# DaslightMux.net
KiCad netlist of a schematic drawn in EAGLE
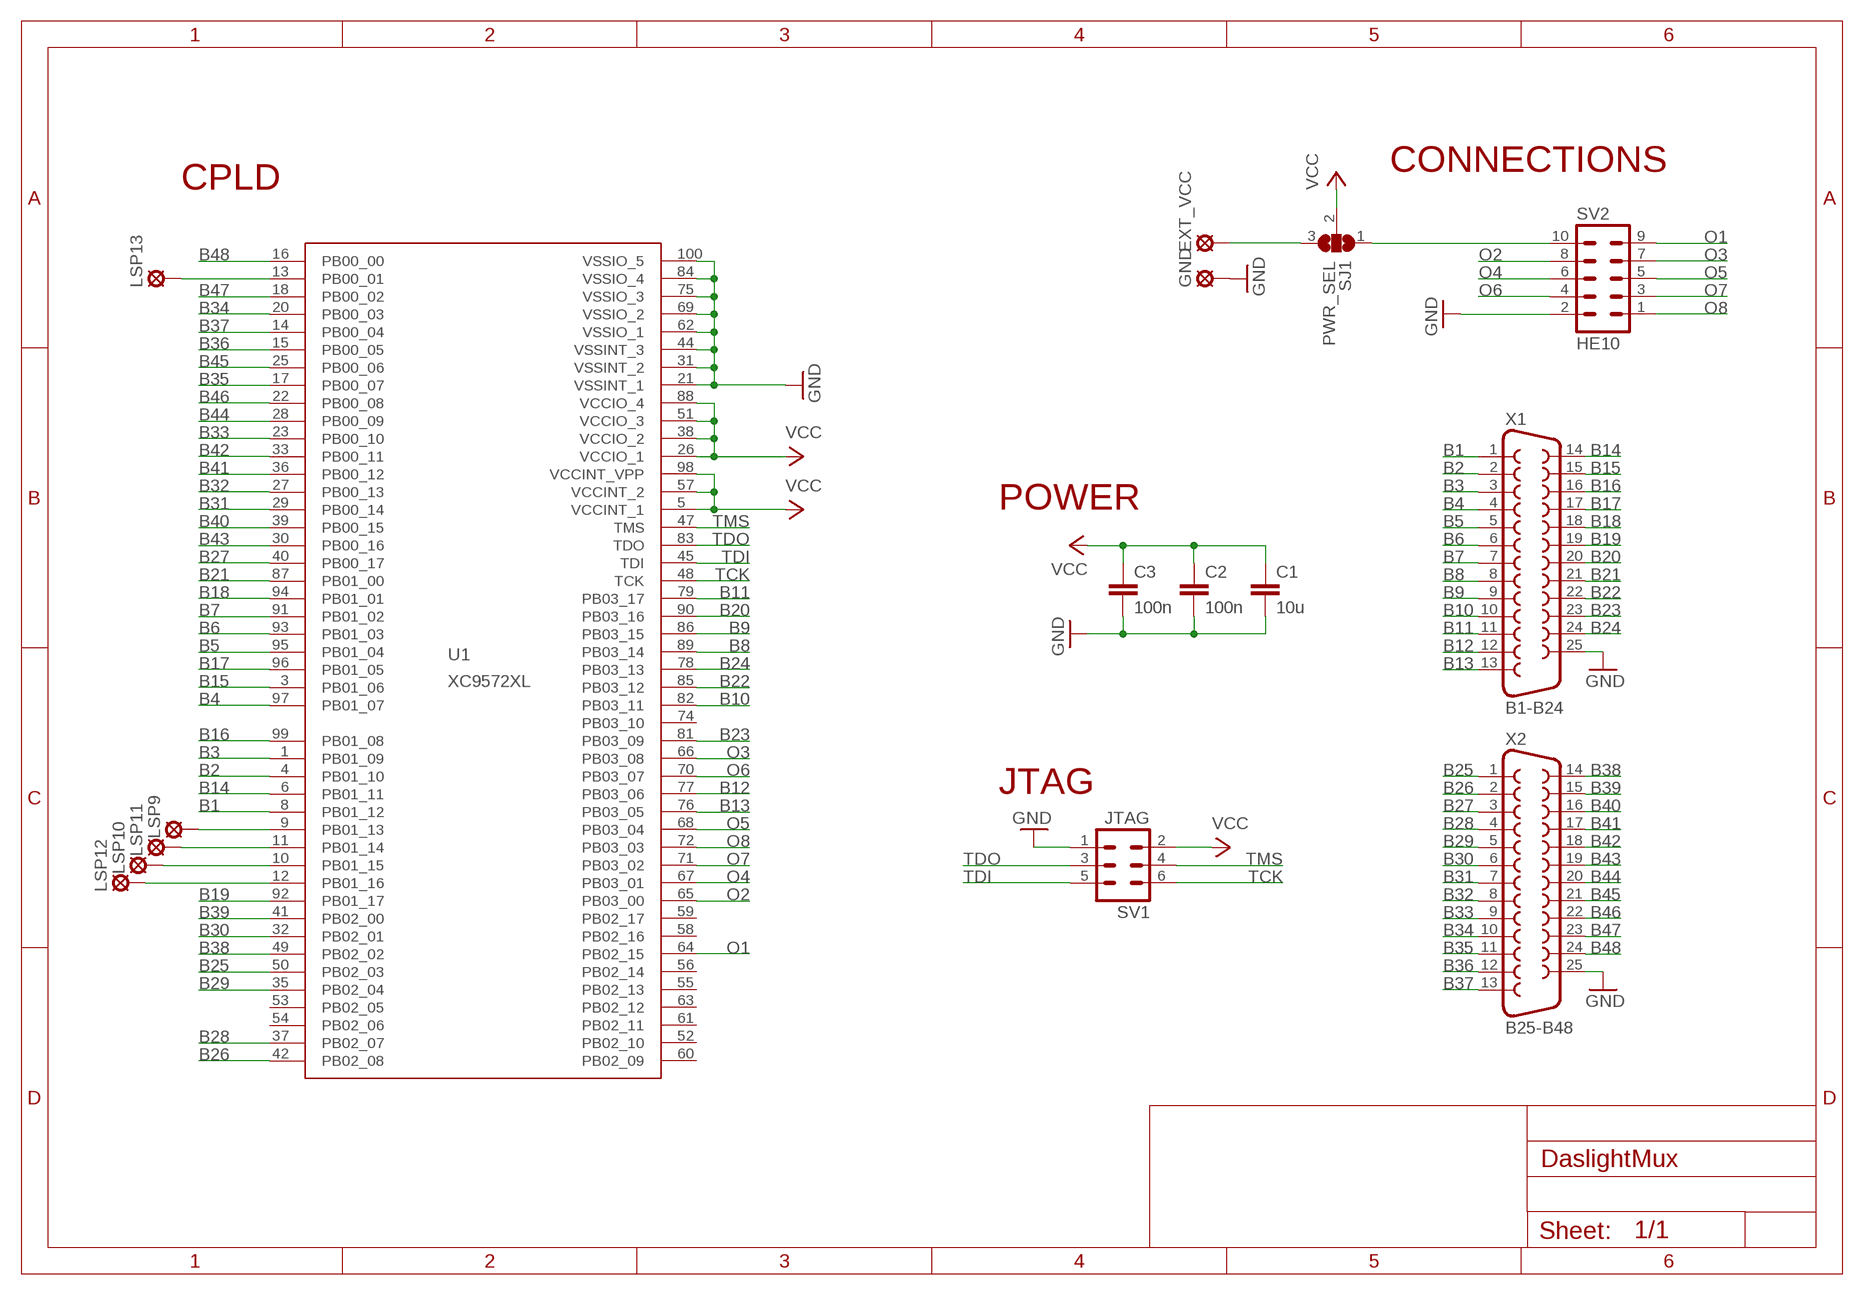
[diagram p0: schematic, sheet 1]

(export (version "E")
  (design (tool "Eeschema 10.0.6"))
  (components
    (comp (ref "C1")
      (value "10u")
      (footprint "eagle-import:C1206")
      (libsource (lib "eagle-import") (part "C-EUC1206"))
    )
    (comp (ref "C2")
      (value "100n")
      (footprint "eagle-import:C0603")
      (libsource (lib "eagle-import") (part "C-EUC0603"))
    )
    (comp (ref "C3")
      (value "100n")
      (footprint "eagle-import:C0603")
      (libsource (lib "eagle-import") (part "C-EUC0603"))
    )
    (comp (ref "EXT_VCC")
      (value "LSP10")
      (footprint "eagle-import:LSP10")
      (libsource (lib "eagle-import") (part "LSP10"))
    )
    (comp (ref "GND")
      (value "LSP10")
      (footprint "eagle-import:LSP10")
      (libsource (lib "eagle-import") (part "LSP10"))
    )
    (comp (ref "LSP9")
      (value "LSP10")
      (footprint "eagle-import:LSP10")
      (libsource (lib "eagle-import") (part "LSP10"))
    )
    (comp (ref "LSP10")
      (value "LSP10")
      (footprint "eagle-import:LSP10")
      (libsource (lib "eagle-import") (part "LSP10"))
    )
    (comp (ref "LSP11")
      (value "LSP10")
      (footprint "eagle-import:LSP10")
      (libsource (lib "eagle-import") (part "LSP10"))
    )
    (comp (ref "LSP12")
      (value "LSP10")
      (footprint "eagle-import:LSP10")
      (libsource (lib "eagle-import") (part "LSP10"))
    )
    (comp (ref "LSP13")
      (value "LSP10")
      (footprint "eagle-import:LSP10")
      (libsource (lib "eagle-import") (part "LSP10"))
    )
    (comp (ref "SJ1")
      (value "PWR_SEL")
      (footprint "eagle-import:SJ_2")
      (libsource (lib "eagle-import") (part "SJ2W"))
    )
    (comp (ref "SV1")
      (value "JTAG")
      (footprint "eagle-import:MA03-2")
      (libsource (lib "eagle-import") (part "MA03-2"))
    )
    (comp (ref "SV2")
      (value "HE10")
      (footprint "eagle-import:ML10L")
      (libsource (lib "eagle-import") (part "ML10L"))
    )
    (comp (ref "U1")
      (value "XC9572XL")
      (footprint "eagle-import:TQ100")
      (libsource (lib "eagle-import") (part "XC9572XL_TQ100"))
    )
    (comp (ref "X1")
      (value "B1-B24")
      (footprint "eagle-import:F25HP")
      (libsource (lib "eagle-import") (part "F25HP"))
    )
    (comp (ref "X2")
      (value "B25-B48")
      (footprint "eagle-import:F25HP")
      (libsource (lib "eagle-import") (part "F25HP"))
    )
  )
  (nets
    (net (code "1") (name "/B1") (class "Default")
      (node (ref "U1") (pin "8") (pinfunction "PB01_12_8") (pintype "bidirectional"))
      (node (ref "X1") (pin "1") (pinfunction "1_1") (pintype "passive"))
    )
    (net (code "2") (name "/B2") (class "Default")
      (node (ref "U1") (pin "4") (pinfunction "PB01_10_4") (pintype "bidirectional"))
      (node (ref "X1") (pin "2") (pinfunction "2_2") (pintype "passive"))
    )
    (net (code "3") (name "/B3") (class "Default")
      (node (ref "U1") (pin "1") (pinfunction "PB01_09_1") (pintype "bidirectional"))
      (node (ref "X1") (pin "3") (pinfunction "3_3") (pintype "passive"))
    )
    (net (code "4") (name "/B4") (class "Default")
      (node (ref "U1") (pin "97") (pinfunction "PB01_07_97") (pintype "bidirectional"))
      (node (ref "X1") (pin "4") (pinfunction "4_4") (pintype "passive"))
    )
    (net (code "5") (name "/B5") (class "Default")
      (node (ref "U1") (pin "95") (pinfunction "PB01_04_95") (pintype "bidirectional"))
      (node (ref "X1") (pin "5") (pinfunction "5_5") (pintype "passive"))
    )
    (net (code "6") (name "/B6") (class "Default")
      (node (ref "U1") (pin "93") (pinfunction "PB01_03_93") (pintype "bidirectional"))
      (node (ref "X1") (pin "6") (pinfunction "6_6") (pintype "passive"))
    )
    (net (code "7") (name "/B7") (class "Default")
      (node (ref "U1") (pin "91") (pinfunction "PB01_02_91") (pintype "bidirectional"))
      (node (ref "X1") (pin "7") (pinfunction "7_7") (pintype "passive"))
    )
    (net (code "8") (name "/B8") (class "Default")
      (node (ref "U1") (pin "89") (pinfunction "PB03_14_89") (pintype "bidirectional"))
      (node (ref "X1") (pin "8") (pinfunction "8_8") (pintype "passive"))
    )
    (net (code "9") (name "/B9") (class "Default")
      (node (ref "U1") (pin "86") (pinfunction "PB03_15_86") (pintype "bidirectional"))
      (node (ref "X1") (pin "9") (pinfunction "9_9") (pintype "passive"))
    )
    (net (code "10") (name "/B10") (class "Default")
      (node (ref "U1") (pin "82") (pinfunction "PB03_11_82") (pintype "bidirectional"))
      (node (ref "X1") (pin "10") (pinfunction "10_10") (pintype "passive"))
    )
    (net (code "11") (name "/B11") (class "Default")
      (node (ref "U1") (pin "79") (pinfunction "PB03_17_79") (pintype "bidirectional"))
      (node (ref "X1") (pin "11") (pinfunction "11_11") (pintype "passive"))
    )
    (net (code "12") (name "/B12") (class "Default")
      (node (ref "U1") (pin "77") (pinfunction "PB03_06_77") (pintype "bidirectional"))
      (node (ref "X1") (pin "12") (pinfunction "12_12") (pintype "passive"))
    )
    (net (code "13") (name "/B13") (class "Default")
      (node (ref "U1") (pin "76") (pinfunction "PB03_05_76") (pintype "bidirectional"))
      (node (ref "X1") (pin "13") (pinfunction "13_13") (pintype "passive"))
    )
    (net (code "14") (name "/B14") (class "Default")
      (node (ref "U1") (pin "6") (pinfunction "PB01_11_6") (pintype "bidirectional"))
      (node (ref "X1") (pin "14") (pinfunction "14_14") (pintype "passive"))
    )
    (net (code "15") (name "/B15") (class "Default")
      (node (ref "U1") (pin "3") (pinfunction "PB01_06_3") (pintype "bidirectional"))
      (node (ref "X1") (pin "15") (pinfunction "15_15") (pintype "passive"))
    )
    (net (code "16") (name "/B16") (class "Default")
      (node (ref "U1") (pin "99") (pinfunction "PB01_08_99") (pintype "bidirectional"))
      (node (ref "X1") (pin "16") (pinfunction "16_16") (pintype "passive"))
    )
    (net (code "17") (name "/B17") (class "Default")
      (node (ref "U1") (pin "96") (pinfunction "PB01_05_96") (pintype "bidirectional"))
      (node (ref "X1") (pin "17") (pinfunction "17_17") (pintype "passive"))
    )
    (net (code "18") (name "/B18") (class "Default")
      (node (ref "U1") (pin "94") (pinfunction "PB01_01_94") (pintype "bidirectional"))
      (node (ref "X1") (pin "18") (pinfunction "18_18") (pintype "passive"))
    )
    (net (code "19") (name "/B19") (class "Default")
      (node (ref "U1") (pin "92") (pinfunction "PB01_17_92") (pintype "bidirectional"))
      (node (ref "X1") (pin "19") (pinfunction "19_19") (pintype "passive"))
    )
    (net (code "20") (name "/B20") (class "Default")
      (node (ref "U1") (pin "90") (pinfunction "PB03_16_90") (pintype "bidirectional"))
      (node (ref "X1") (pin "20") (pinfunction "20_20") (pintype "passive"))
    )
    (net (code "21") (name "/B21") (class "Default")
      (node (ref "U1") (pin "87") (pinfunction "PB01_00_87") (pintype "bidirectional"))
      (node (ref "X1") (pin "21") (pinfunction "21_21") (pintype "passive"))
    )
    (net (code "22") (name "/B22") (class "Default")
      (node (ref "U1") (pin "85") (pinfunction "PB03_12_85") (pintype "bidirectional"))
      (node (ref "X1") (pin "22") (pinfunction "22_22") (pintype "passive"))
    )
    (net (code "23") (name "/B23") (class "Default")
      (node (ref "U1") (pin "81") (pinfunction "PB03_09_81") (pintype "bidirectional"))
      (node (ref "X1") (pin "23") (pinfunction "23_23") (pintype "passive"))
    )
    (net (code "24") (name "/B24") (class "Default")
      (node (ref "U1") (pin "78") (pinfunction "PB03_13_78") (pintype "bidirectional"))
      (node (ref "X1") (pin "24") (pinfunction "24_24") (pintype "passive"))
    )
    (net (code "25") (name "/B25") (class "Default")
      (node (ref "U1") (pin "50") (pinfunction "PB02_03_50") (pintype "bidirectional"))
      (node (ref "X2") (pin "1") (pinfunction "1_1") (pintype "passive"))
    )
    (net (code "26") (name "/B26") (class "Default")
      (node (ref "U1") (pin "42") (pinfunction "PB02_08_42") (pintype "bidirectional"))
      (node (ref "X2") (pin "2") (pinfunction "2_2") (pintype "passive"))
    )
    (net (code "27") (name "/B27") (class "Default")
      (node (ref "U1") (pin "40") (pinfunction "PB00_17_40") (pintype "bidirectional"))
      (node (ref "X2") (pin "3") (pinfunction "3_3") (pintype "passive"))
    )
    (net (code "28") (name "/B28") (class "Default")
      (node (ref "U1") (pin "37") (pinfunction "PB02_07_37") (pintype "bidirectional"))
      (node (ref "X2") (pin "4") (pinfunction "4_4") (pintype "passive"))
    )
    (net (code "29") (name "/B29") (class "Default")
      (node (ref "U1") (pin "35") (pinfunction "PB02_04_35") (pintype "bidirectional"))
      (node (ref "X2") (pin "5") (pinfunction "5_5") (pintype "passive"))
    )
    (net (code "30") (name "/B30") (class "Default")
      (node (ref "U1") (pin "32") (pinfunction "PB02_01_32") (pintype "bidirectional"))
      (node (ref "X2") (pin "6") (pinfunction "6_6") (pintype "passive"))
    )
    (net (code "31") (name "/B31") (class "Default")
      (node (ref "U1") (pin "29") (pinfunction "PB00_14_29") (pintype "bidirectional"))
      (node (ref "X2") (pin "7") (pinfunction "7_7") (pintype "passive"))
    )
    (net (code "32") (name "/B32") (class "Default")
      (node (ref "U1") (pin "27") (pinfunction "PB00_13_27") (pintype "bidirectional"))
      (node (ref "X2") (pin "8") (pinfunction "8_8") (pintype "passive"))
    )
    (net (code "33") (name "/B33") (class "Default")
      (node (ref "U1") (pin "23") (pinfunction "PB00_10_23") (pintype "bidirectional"))
      (node (ref "X2") (pin "9") (pinfunction "9_9") (pintype "passive"))
    )
    (net (code "34") (name "/B34") (class "Default")
      (node (ref "U1") (pin "20") (pinfunction "PB00_03_20") (pintype "bidirectional"))
      (node (ref "X2") (pin "10") (pinfunction "10_10") (pintype "passive"))
    )
    (net (code "35") (name "/B35") (class "Default")
      (node (ref "U1") (pin "17") (pinfunction "PB00_07_17") (pintype "bidirectional"))
      (node (ref "X2") (pin "11") (pinfunction "11_11") (pintype "passive"))
    )
    (net (code "36") (name "/B36") (class "Default")
      (node (ref "U1") (pin "15") (pinfunction "PB00_05_15") (pintype "bidirectional"))
      (node (ref "X2") (pin "12") (pinfunction "12_12") (pintype "passive"))
    )
    (net (code "37") (name "/B37") (class "Default")
      (node (ref "U1") (pin "14") (pinfunction "PB00_04_14") (pintype "bidirectional"))
      (node (ref "X2") (pin "13") (pinfunction "13_13") (pintype "passive"))
    )
    (net (code "38") (name "/B38") (class "Default")
      (node (ref "U1") (pin "49") (pinfunction "PB02_02_49") (pintype "bidirectional"))
      (node (ref "X2") (pin "14") (pinfunction "14_14") (pintype "passive"))
    )
    (net (code "39") (name "/B39") (class "Default")
      (node (ref "U1") (pin "41") (pinfunction "PB02_00_41") (pintype "bidirectional"))
      (node (ref "X2") (pin "15") (pinfunction "15_15") (pintype "passive"))
    )
    (net (code "40") (name "/B40") (class "Default")
      (node (ref "U1") (pin "39") (pinfunction "PB00_15_39") (pintype "bidirectional"))
      (node (ref "X2") (pin "16") (pinfunction "16_16") (pintype "passive"))
    )
    (net (code "41") (name "/B41") (class "Default")
      (node (ref "U1") (pin "36") (pinfunction "PB00_12_36") (pintype "bidirectional"))
      (node (ref "X2") (pin "17") (pinfunction "17_17") (pintype "passive"))
    )
    (net (code "42") (name "/B42") (class "Default")
      (node (ref "U1") (pin "33") (pinfunction "PB00_11_33") (pintype "bidirectional"))
      (node (ref "X2") (pin "18") (pinfunction "18_18") (pintype "passive"))
    )
    (net (code "43") (name "/B43") (class "Default")
      (node (ref "U1") (pin "30") (pinfunction "PB00_16_30") (pintype "bidirectional"))
      (node (ref "X2") (pin "19") (pinfunction "19_19") (pintype "passive"))
    )
    (net (code "44") (name "/B44") (class "Default")
      (node (ref "U1") (pin "28") (pinfunction "PB00_09_28") (pintype "bidirectional"))
      (node (ref "X2") (pin "20") (pinfunction "20_20") (pintype "passive"))
    )
    (net (code "45") (name "/B45") (class "Default")
      (node (ref "U1") (pin "25") (pinfunction "PB00_06_25") (pintype "bidirectional"))
      (node (ref "X2") (pin "21") (pinfunction "21_21") (pintype "passive"))
    )
    (net (code "46") (name "/B46") (class "Default")
      (node (ref "U1") (pin "22") (pinfunction "PB00_08_22") (pintype "bidirectional"))
      (node (ref "X2") (pin "22") (pinfunction "22_22") (pintype "passive"))
    )
    (net (code "47") (name "/B47") (class "Default")
      (node (ref "U1") (pin "18") (pinfunction "PB00_02_18") (pintype "bidirectional"))
      (node (ref "X2") (pin "23") (pinfunction "23_23") (pintype "passive"))
    )
    (net (code "48") (name "/B48") (class "Default")
      (node (ref "U1") (pin "16") (pinfunction "PB00_00_16") (pintype "bidirectional"))
      (node (ref "X2") (pin "24") (pinfunction "24_24") (pintype "passive"))
    )
    (net (code "49") (name "/O1") (class "Default")
      (node (ref "SV2") (pin "9") (pinfunction "9_9") (pintype "passive"))
      (node (ref "U1") (pin "64") (pinfunction "PB02_15_64") (pintype "bidirectional"))
    )
    (net (code "50") (name "/O2") (class "Default")
      (node (ref "SV2") (pin "8") (pinfunction "8_8") (pintype "passive"))
      (node (ref "U1") (pin "65") (pinfunction "PB03_00_65") (pintype "bidirectional"))
    )
    (net (code "51") (name "/O3") (class "Default")
      (node (ref "SV2") (pin "7") (pinfunction "7_7") (pintype "passive"))
      (node (ref "U1") (pin "66") (pinfunction "PB03_08_66") (pintype "bidirectional"))
    )
    (net (code "52") (name "/O4") (class "Default")
      (node (ref "SV2") (pin "6") (pinfunction "6_6") (pintype "passive"))
      (node (ref "U1") (pin "67") (pinfunction "PB03_01_67") (pintype "bidirectional"))
    )
    (net (code "53") (name "/O5") (class "Default")
      (node (ref "SV2") (pin "5") (pinfunction "5_5") (pintype "passive"))
      (node (ref "U1") (pin "68") (pinfunction "PB03_04_68") (pintype "bidirectional"))
    )
    (net (code "54") (name "/O6") (class "Default")
      (node (ref "SV2") (pin "4") (pinfunction "4_4") (pintype "passive"))
      (node (ref "U1") (pin "70") (pinfunction "PB03_07_70") (pintype "bidirectional"))
    )
    (net (code "55") (name "/O7") (class "Default")
      (node (ref "SV2") (pin "3") (pinfunction "3_3") (pintype "passive"))
      (node (ref "U1") (pin "71") (pinfunction "PB03_02_71") (pintype "bidirectional"))
    )
    (net (code "56") (name "/O8") (class "Default")
      (node (ref "SV2") (pin "1") (pinfunction "1_1") (pintype "passive"))
      (node (ref "U1") (pin "72") (pinfunction "PB03_03_72") (pintype "bidirectional"))
    )
    (net (code "57") (name "/TCK") (class "Default")
      (node (ref "SV1") (pin "6") (pinfunction "6_6") (pintype "passive"))
      (node (ref "U1") (pin "48") (pinfunction "TCK_48") (pintype "input"))
    )
    (net (code "58") (name "/TDI") (class "Default")
      (node (ref "SV1") (pin "5") (pinfunction "5_5") (pintype "passive"))
      (node (ref "U1") (pin "45") (pinfunction "TDI_45") (pintype "input"))
    )
    (net (code "59") (name "/TDO") (class "Default")
      (node (ref "SV1") (pin "3") (pinfunction "3_3") (pintype "passive"))
      (node (ref "U1") (pin "83") (pinfunction "TDO_83") (pintype "output"))
    )
    (net (code "60") (name "/TMS") (class "Default")
      (node (ref "SV1") (pin "4") (pinfunction "4_4") (pintype "passive"))
      (node (ref "U1") (pin "47") (pinfunction "TMS_47") (pintype "input"))
    )
    (net (code "61") (name "GND") (class "Default")
      (node (ref "C1") (pin "2") (pinfunction "2_2") (pintype "passive"))
      (node (ref "C2") (pin "2") (pinfunction "2_2") (pintype "passive"))
      (node (ref "C3") (pin "2") (pinfunction "2_2") (pintype "passive"))
      (node (ref "GND") (pin "MP") (pinfunction "MP_MP") (pintype "passive"))
      (node (ref "SV1") (pin "1") (pinfunction "1_1") (pintype "passive"))
      (node (ref "SV2") (pin "2") (pinfunction "2_2") (pintype "passive"))
      (node (ref "U1") (pin "100") (pinfunction "VSSIO_5_100") (pintype "passive"))
      (node (ref "U1") (pin "21") (pinfunction "VSSINT_1_21") (pintype "passive"))
      (node (ref "U1") (pin "31") (pinfunction "VSSINT_2_31") (pintype "passive"))
      (node (ref "U1") (pin "44") (pinfunction "VSSINT_3_44") (pintype "passive"))
      (node (ref "U1") (pin "62") (pinfunction "VSSIO_1_62") (pintype "passive"))
      (node (ref "U1") (pin "69") (pinfunction "VSSIO_2_69") (pintype "passive"))
      (node (ref "U1") (pin "75") (pinfunction "VSSIO_3_75") (pintype "passive"))
      (node (ref "U1") (pin "84") (pinfunction "VSSIO_4_84") (pintype "passive"))
      (node (ref "X1") (pin "25") (pinfunction "25_25") (pintype "passive"))
      (node (ref "X2") (pin "25") (pinfunction "25_25") (pintype "passive"))
    )
    (net (code "62") (name "Net-(EXT_VCC-PadMP)") (class "Default")
      (node (ref "EXT_VCC") (pin "MP") (pinfunction "MP_MP") (pintype "passive"))
      (node (ref "SJ1") (pin "3") (pinfunction "3_3") (pintype "passive"))
    )
    (net (code "63") (name "Net-(SJ1-Pad1)") (class "Default")
      (node (ref "SJ1") (pin "1") (pinfunction "1_1") (pintype "passive"))
      (node (ref "SV2") (pin "10") (pinfunction "10_10") (pintype "passive"))
    )
    (net (code "64") (name "Net-(U1-PB00_01)") (class "Default")
      (node (ref "LSP13") (pin "MP") (pinfunction "MP_MP") (pintype "passive"))
      (node (ref "U1") (pin "13") (pinfunction "PB00_01_13") (pintype "bidirectional"))
    )
    (net (code "65") (name "Net-(U1-PB01_13)") (class "Default")
      (node (ref "LSP9") (pin "MP") (pinfunction "MP_MP") (pintype "passive"))
      (node (ref "U1") (pin "9") (pinfunction "PB01_13_9") (pintype "bidirectional"))
    )
    (net (code "66") (name "Net-(U1-PB01_14)") (class "Default")
      (node (ref "LSP11") (pin "MP") (pinfunction "MP_MP") (pintype "passive"))
      (node (ref "U1") (pin "11") (pinfunction "PB01_14_11") (pintype "bidirectional"))
    )
    (net (code "67") (name "Net-(U1-PB01_15)") (class "Default")
      (node (ref "LSP10") (pin "MP") (pinfunction "MP_MP") (pintype "passive"))
      (node (ref "U1") (pin "10") (pinfunction "PB01_15_10") (pintype "bidirectional"))
    )
    (net (code "68") (name "Net-(U1-PB01_16)") (class "Default")
      (node (ref "LSP12") (pin "MP") (pinfunction "MP_MP") (pintype "passive"))
      (node (ref "U1") (pin "12") (pinfunction "PB01_16_12") (pintype "bidirectional"))
    )
    (net (code "69") (name "VCC") (class "Default")
      (node (ref "C1") (pin "1") (pinfunction "1_1") (pintype "passive"))
      (node (ref "C2") (pin "1") (pinfunction "1_1") (pintype "passive"))
      (node (ref "C3") (pin "1") (pinfunction "1_1") (pintype "passive"))
      (node (ref "SJ1") (pin "2") (pinfunction "2_2") (pintype "passive"))
      (node (ref "SV1") (pin "2") (pinfunction "2_2") (pintype "passive"))
      (node (ref "U1") (pin "26") (pinfunction "VCCIO_1_26") (pintype "passive"))
      (node (ref "U1") (pin "38") (pinfunction "VCCIO_2_38") (pintype "passive"))
      (node (ref "U1") (pin "5") (pinfunction "VCCINT_1_5") (pintype "passive"))
      (node (ref "U1") (pin "51") (pinfunction "VCCIO_3_51") (pintype "passive"))
      (node (ref "U1") (pin "57") (pinfunction "VCCINT_2_57") (pintype "passive"))
      (node (ref "U1") (pin "88") (pinfunction "VCCIO_4_88") (pintype "passive"))
      (node (ref "U1") (pin "98") (pinfunction "VCCINT_VPP_98") (pintype "passive"))
    )
    (net (code "70") (name "unconnected-(U1-PB02_05-Pad53)") (class "Default")
      (node (ref "U1") (pin "53") (pinfunction "PB02_05_53") (pintype "bidirectional"))
    )
    (net (code "71") (name "unconnected-(U1-PB02_06-Pad54)") (class "Default")
      (node (ref "U1") (pin "54") (pinfunction "PB02_06_54") (pintype "bidirectional"))
    )
    (net (code "72") (name "unconnected-(U1-PB02_09-Pad60)") (class "Default")
      (node (ref "U1") (pin "60") (pinfunction "PB02_09_60") (pintype "bidirectional"))
    )
    (net (code "73") (name "unconnected-(U1-PB02_10-Pad52)") (class "Default")
      (node (ref "U1") (pin "52") (pinfunction "PB02_10_52") (pintype "bidirectional"))
    )
    (net (code "74") (name "unconnected-(U1-PB02_11-Pad61)") (class "Default")
      (node (ref "U1") (pin "61") (pinfunction "PB02_11_61") (pintype "bidirectional"))
    )
    (net (code "75") (name "unconnected-(U1-PB02_12-Pad63)") (class "Default")
      (node (ref "U1") (pin "63") (pinfunction "PB02_12_63") (pintype "bidirectional"))
    )
    (net (code "76") (name "unconnected-(U1-PB02_13-Pad55)") (class "Default")
      (node (ref "U1") (pin "55") (pinfunction "PB02_13_55") (pintype "bidirectional"))
    )
    (net (code "77") (name "unconnected-(U1-PB02_14-Pad56)") (class "Default")
      (node (ref "U1") (pin "56") (pinfunction "PB02_14_56") (pintype "bidirectional"))
    )
    (net (code "78") (name "unconnected-(U1-PB02_16-Pad58)") (class "Default")
      (node (ref "U1") (pin "58") (pinfunction "PB02_16_58") (pintype "bidirectional"))
    )
    (net (code "79") (name "unconnected-(U1-PB02_17-Pad59)") (class "Default")
      (node (ref "U1") (pin "59") (pinfunction "PB02_17_59") (pintype "bidirectional"))
    )
    (net (code "80") (name "unconnected-(U1-PB03_10-Pad74)") (class "Default")
      (node (ref "U1") (pin "74") (pinfunction "PB03_10_74") (pintype "bidirectional"))
    )
  )
)
